# uC.net
KiCad netlist of a schematic drawn in Altium Designer
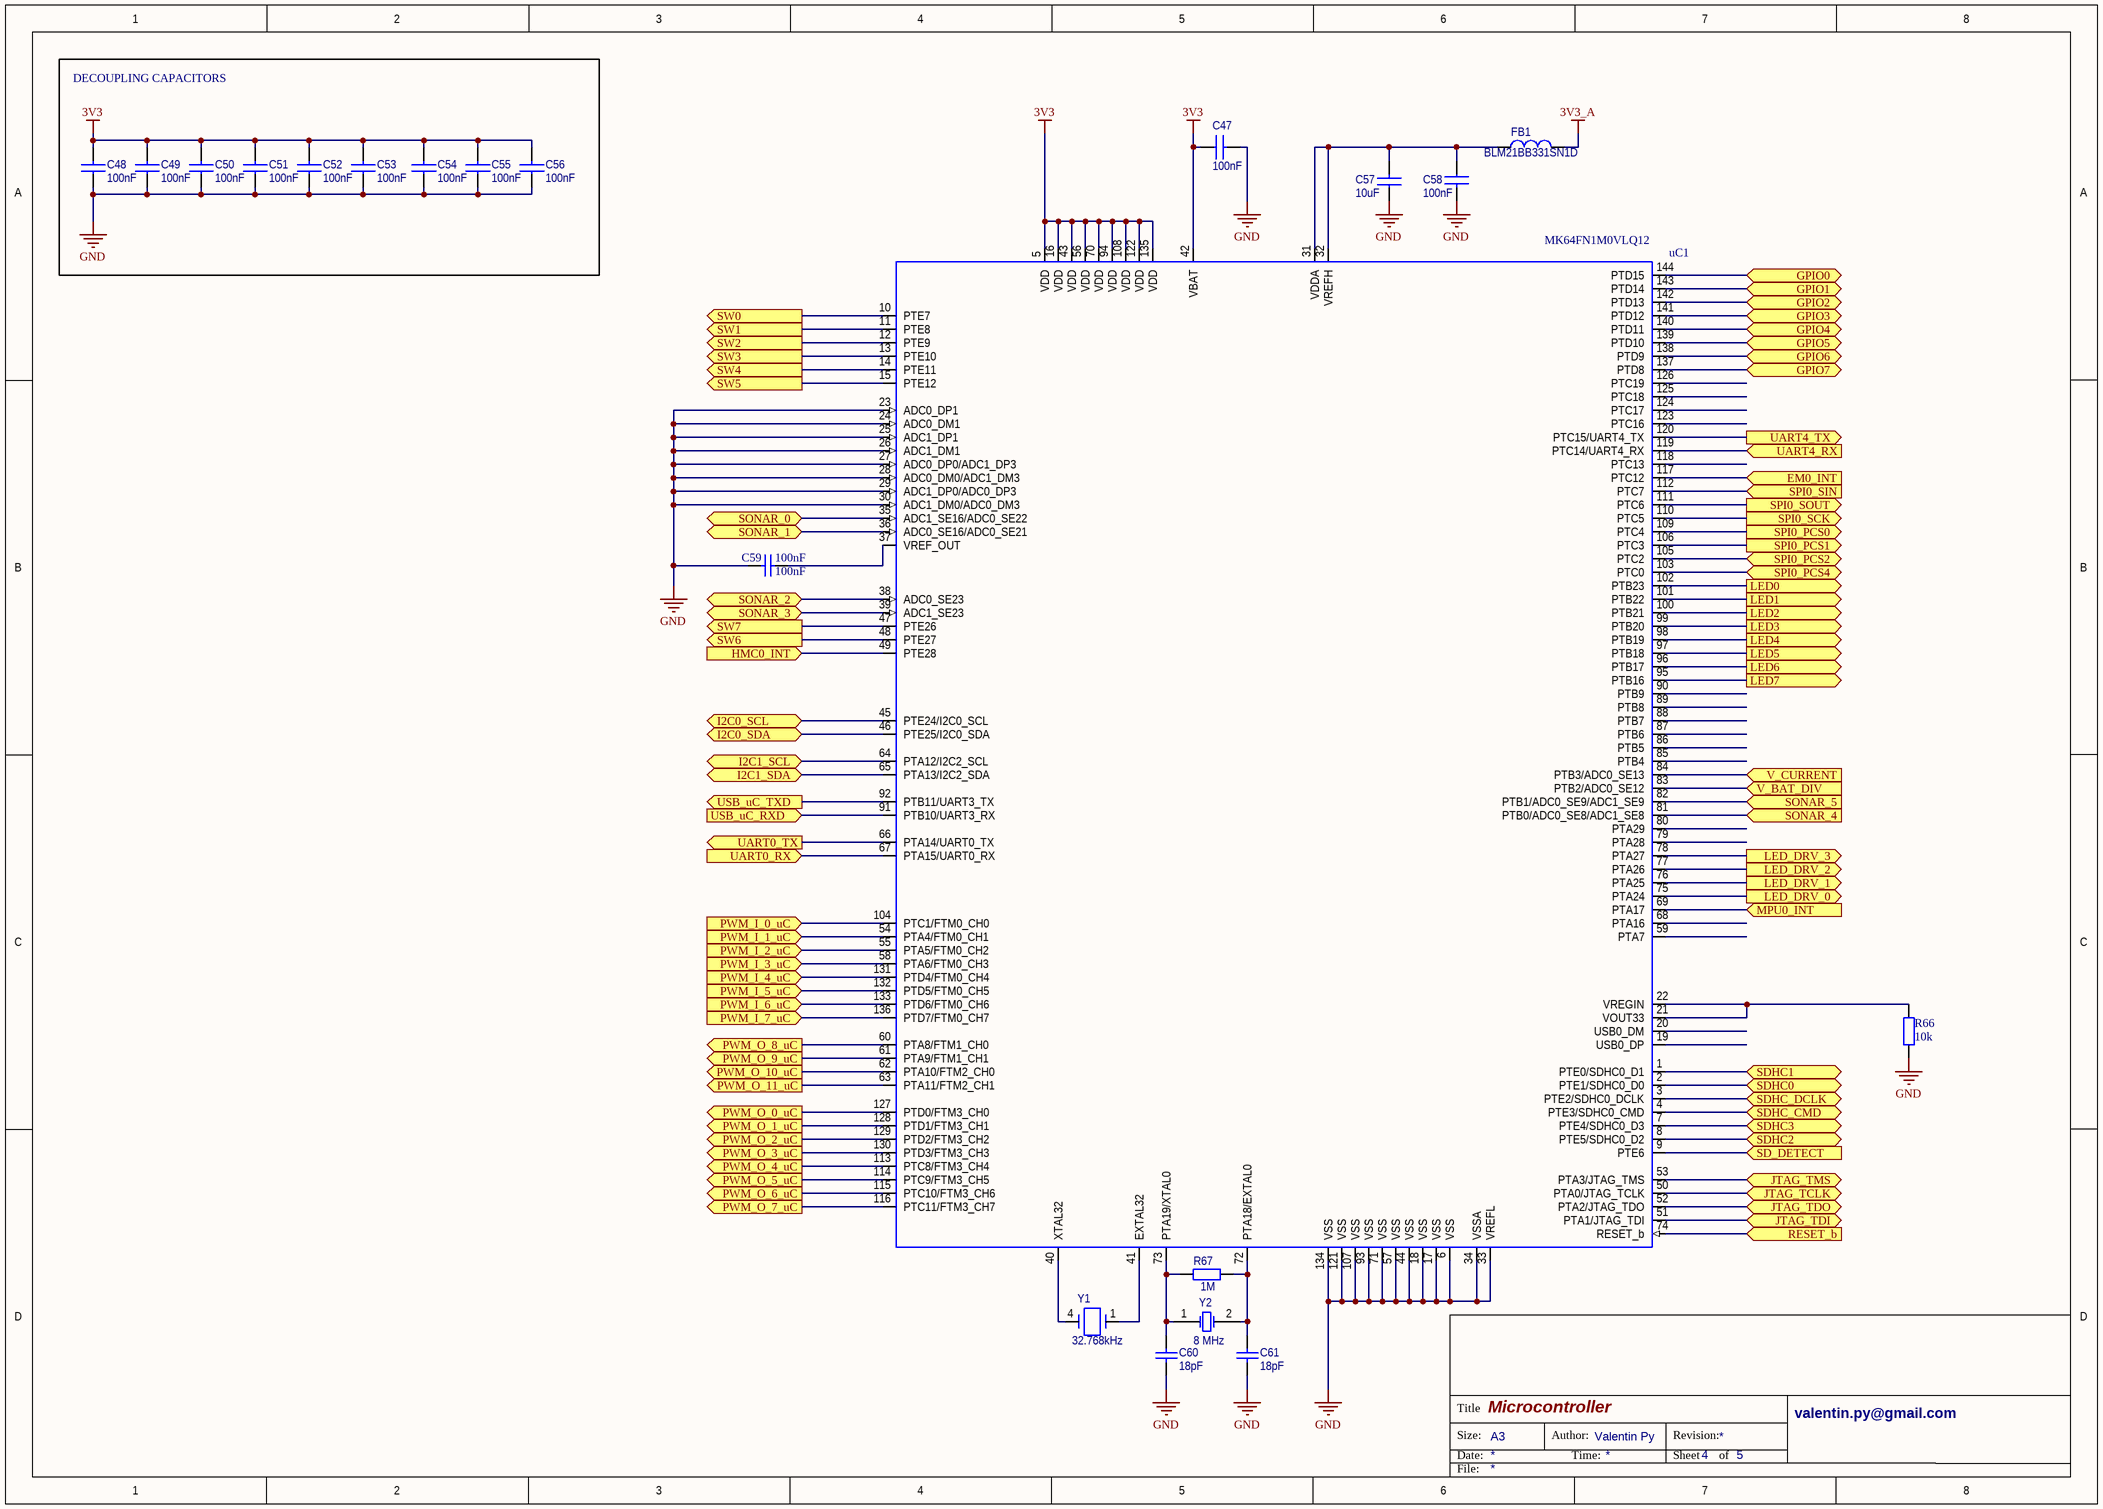
[diagram p0: uC.SchDoc]

(export (version "E")
  (design (tool "Eeschema 10.0.6"))
  (components
    (comp (ref "C47")
      (value "100nF")
      (footprint "080503")
      (description "CAP CER 0.1UF 25V 10% X7R 0805")
      (libsource (lib "EISI") (part "CAPA"))
    )
    (comp (ref "C48")
      (value "100nF")
      (footprint "080503")
      (description "CAP CER 0.1UF 25V 10% X7R 0805")
      (libsource (lib "EISI") (part "CAPA"))
    )
    (comp (ref "C49")
      (value "100nF")
      (footprint "080503")
      (description "CAP CER 0.1UF 25V 10% X7R 0805")
      (libsource (lib "EISI") (part "CAPA"))
    )
    (comp (ref "C50")
      (value "100nF")
      (footprint "080503")
      (description "CAP CER 0.1UF 25V 10% X7R 0805")
      (libsource (lib "EISI") (part "CAPA"))
    )
    (comp (ref "C51")
      (value "100nF")
      (footprint "080503")
      (description "CAP CER 0.1UF 25V 10% X7R 0805")
      (libsource (lib "EISI") (part "CAPA"))
    )
    (comp (ref "C52")
      (value "100nF")
      (footprint "080503")
      (description "CAP CER 0.1UF 25V 10% X7R 0805")
      (libsource (lib "EISI") (part "CAPA"))
    )
    (comp (ref "C53")
      (value "100nF")
      (footprint "080503")
      (description "CAP CER 0.1UF 25V 10% X7R 0805")
      (libsource (lib "EISI") (part "CAPA"))
    )
    (comp (ref "C54")
      (value "100nF")
      (footprint "080503")
      (description "CAP CER 0.1UF 25V 10% X7R 0805")
      (libsource (lib "EISI") (part "CAPA"))
    )
    (comp (ref "C55")
      (value "100nF")
      (footprint "080503")
      (description "CAP CER 0.1UF 25V 10% X7R 0805")
      (libsource (lib "EISI") (part "CAPA"))
    )
    (comp (ref "C56")
      (value "100nF")
      (footprint "080503")
      (description "CAP CER 0.1UF 25V 10% X7R 0805")
      (libsource (lib "EISI") (part "CAPA"))
    )
    (comp (ref "C57")
      (value "10uF")
      (footprint "080503")
      (description "CAP CER 10UF 16V 20% X6S 0805")
      (libsource (lib "EISI") (part "CAPA"))
    )
    (comp (ref "C58")
      (value "100nF")
      (footprint "080503")
      (description "CAP CER 0.1UF 25V 10% X7R 0805")
      (libsource (lib "EISI") (part "CAPA"))
    )
    (comp (ref "C59")
      (value "100nF")
      (footprint "080503")
      (description "CAP CER 0.1UF 25V 10% X7R 0805")
      (fields (field (name "ALTIUM_VALUE") "100nF"))
      (libsource (lib "Miscellaneous Devices") (part "Cap"))
    )
    (comp (ref "C60")
      (value "18pF")
      (footprint "060301")
      (description "CAP CER 18PF 50V 5% NP0 0603")
      (libsource (lib "Miscellaneous Devices") (part "Cap Semi"))
    )
    (comp (ref "C61")
      (value "18pF")
      (footprint "060301")
      (description "CAP CER 18PF 50V 5% NP0 0603")
      (libsource (lib "Miscellaneous Devices") (part "Cap Semi"))
    )
    (comp (ref "FB1")
      (value "BLM21BB331SN1D")
      (footprint "080501")
      (description "EMI Filter Beads, Chips & Arrays 0805 330 OHM")
      (libsource (lib "EISI") (part "Ferrite Bead"))
    )
    (comp (ref "R66")
      (value "10k")
      (footprint "060301")
      (description "RES 10K 0805")
      (libsource (lib "EISI") (part "RES"))
    )
    (comp (ref "R67")
      (value "1M")
      (footprint "060301")
      (description "RES 1M 0603")
      (libsource (lib "") (part "RES_1"))
    )
    (comp (ref "uC1")
      (value "MK64FN1M0VLQ12")
      (footprint "LQFP 144")
      (libsource (lib "Aeroval") (part "MK64FN1M0VLQ12"))
    )
    (comp (ref "Y1")
      (value "32.768kHz")
      (description "CRYSTAL 32.768 KHZ 12.5PF SMD")
      (fields (field (name "Comment") "CRYSTAL 32.768k"))
      (libsource (lib "*") (part "Crystal_32"))
    )
    (comp (ref "Y2")
      (value "8 MHz")
      (footprint "XT8_2-SMD")
      (description "CRYSTAL 8MHZ 18PF SMD")
      (fields (field (name "Comment") "ABM3-8.000MHZ-D2Y-T"))
      (libsource (lib "Miscellaneous Devices") (part "XTAL"))
    )
  )
  (nets
    (net (code "1") (name "/EM0_INT") (class "Default")
      (node (ref "uC1") (pin "117") (pinfunction "PTC12_117") (pintype "bidirectional"))
    )
    (net (code "2") (name "/GPIO0") (class "Default")
      (node (ref "uC1") (pin "144") (pinfunction "PTD15_144") (pintype "bidirectional"))
    )
    (net (code "3") (name "/GPIO1") (class "Default")
      (node (ref "uC1") (pin "143") (pinfunction "PTD14_143") (pintype "bidirectional"))
    )
    (net (code "4") (name "/GPIO2") (class "Default")
      (node (ref "uC1") (pin "142") (pinfunction "PTD13_142") (pintype "bidirectional"))
    )
    (net (code "5") (name "/GPIO3") (class "Default")
      (node (ref "uC1") (pin "141") (pinfunction "PTD12_141") (pintype "bidirectional"))
    )
    (net (code "6") (name "/GPIO4") (class "Default")
      (node (ref "uC1") (pin "140") (pinfunction "PTD11_140") (pintype "bidirectional"))
    )
    (net (code "7") (name "/GPIO5") (class "Default")
      (node (ref "uC1") (pin "139") (pinfunction "PTD10_139") (pintype "bidirectional"))
    )
    (net (code "8") (name "/GPIO6") (class "Default")
      (node (ref "uC1") (pin "138") (pinfunction "PTD9_138") (pintype "bidirectional"))
    )
    (net (code "9") (name "/GPIO7") (class "Default")
      (node (ref "uC1") (pin "137") (pinfunction "PTD8_137") (pintype "bidirectional"))
    )
    (net (code "10") (name "/HMC0_INT") (class "Default")
      (node (ref "uC1") (pin "49") (pinfunction "PTE28_49") (pintype "bidirectional"))
    )
    (net (code "11") (name "/I2C0_SCL") (class "Default")
      (node (ref "uC1") (pin "45") (pinfunction "PTE24/I2C0_SCL_45") (pintype "bidirectional"))
    )
    (net (code "12") (name "/I2C0_SDA") (class "Default")
      (node (ref "uC1") (pin "46") (pinfunction "PTE25/I2C0_SDA_46") (pintype "bidirectional"))
    )
    (net (code "13") (name "/I2C1_SCL") (class "Default")
      (node (ref "uC1") (pin "64") (pinfunction "PTA12/I2C2_SCL_64") (pintype "bidirectional"))
    )
    (net (code "14") (name "/I2C1_SDA") (class "Default")
      (node (ref "uC1") (pin "65") (pinfunction "PTA13/I2C2_SDA_65") (pintype "bidirectional"))
    )
    (net (code "15") (name "/JTAG_TCLK") (class "Default")
      (node (ref "uC1") (pin "50") (pinfunction "PTA0/JTAG_TCLK_50") (pintype "bidirectional"))
    )
    (net (code "16") (name "/JTAG_TDI") (class "Default")
      (node (ref "uC1") (pin "51") (pinfunction "PTA1/JTAG_TDI_51") (pintype "bidirectional"))
    )
    (net (code "17") (name "/JTAG_TDO") (class "Default")
      (node (ref "uC1") (pin "52") (pinfunction "PTA2/JTAG_TDO_52") (pintype "bidirectional"))
    )
    (net (code "18") (name "/JTAG_TMS") (class "Default")
      (node (ref "uC1") (pin "53") (pinfunction "PTA3/JTAG_TMS_53") (pintype "bidirectional"))
    )
    (net (code "19") (name "/LED0") (class "Default")
      (node (ref "uC1") (pin "102") (pinfunction "PTB23_102") (pintype "bidirectional"))
    )
    (net (code "20") (name "/LED1") (class "Default")
      (node (ref "uC1") (pin "101") (pinfunction "PTB22_101") (pintype "bidirectional"))
    )
    (net (code "21") (name "/LED2") (class "Default")
      (node (ref "uC1") (pin "100") (pinfunction "PTB21_100") (pintype "bidirectional"))
    )
    (net (code "22") (name "/LED3") (class "Default")
      (node (ref "uC1") (pin "99") (pinfunction "PTB20_99") (pintype "bidirectional"))
    )
    (net (code "23") (name "/LED4") (class "Default")
      (node (ref "uC1") (pin "98") (pinfunction "PTB19_98") (pintype "bidirectional"))
    )
    (net (code "24") (name "/LED5") (class "Default")
      (node (ref "uC1") (pin "97") (pinfunction "PTB18_97") (pintype "bidirectional"))
    )
    (net (code "25") (name "/LED6") (class "Default")
      (node (ref "uC1") (pin "96") (pinfunction "PTB17_96") (pintype "bidirectional"))
    )
    (net (code "26") (name "/LED7") (class "Default")
      (node (ref "uC1") (pin "95") (pinfunction "PTB16_95") (pintype "bidirectional"))
    )
    (net (code "27") (name "/LED_DRV_0") (class "Default")
      (node (ref "uC1") (pin "75") (pinfunction "PTA24_75") (pintype "bidirectional"))
    )
    (net (code "28") (name "/LED_DRV_1") (class "Default")
      (node (ref "uC1") (pin "76") (pinfunction "PTA25_76") (pintype "bidirectional"))
    )
    (net (code "29") (name "/LED_DRV_2") (class "Default")
      (node (ref "uC1") (pin "77") (pinfunction "PTA26_77") (pintype "bidirectional"))
    )
    (net (code "30") (name "/LED_DRV_3") (class "Default")
      (node (ref "uC1") (pin "78") (pinfunction "PTA27_78") (pintype "bidirectional"))
    )
    (net (code "31") (name "/MPU0_INT") (class "Default")
      (node (ref "uC1") (pin "69") (pinfunction "PTA17_69") (pintype "bidirectional"))
    )
    (net (code "32") (name "/PWM_I_0_uC") (class "Default")
      (node (ref "uC1") (pin "104") (pinfunction "PTC1/FTM0_CH0_104") (pintype "bidirectional"))
    )
    (net (code "33") (name "/PWM_I_1_uC") (class "Default")
      (node (ref "uC1") (pin "54") (pinfunction "PTA4/FTM0_CH1_54") (pintype "bidirectional"))
    )
    (net (code "34") (name "/PWM_I_2_uC") (class "Default")
      (node (ref "uC1") (pin "55") (pinfunction "PTA5/FTM0_CH2_55") (pintype "bidirectional"))
    )
    (net (code "35") (name "/PWM_I_3_uC") (class "Default")
      (node (ref "uC1") (pin "58") (pinfunction "PTA6/FTM0_CH3_58") (pintype "bidirectional"))
    )
    (net (code "36") (name "/PWM_I_4_uC") (class "Default")
      (node (ref "uC1") (pin "131") (pinfunction "PTD4/FTM0_CH4_131") (pintype "bidirectional"))
    )
    (net (code "37") (name "/PWM_I_5_uC") (class "Default")
      (node (ref "uC1") (pin "132") (pinfunction "PTD5/FTM0_CH5_132") (pintype "bidirectional"))
    )
    (net (code "38") (name "/PWM_I_6_uC") (class "Default")
      (node (ref "uC1") (pin "133") (pinfunction "PTD6/FTM0_CH6_133") (pintype "bidirectional"))
    )
    (net (code "39") (name "/PWM_I_7_uC") (class "Default")
      (node (ref "uC1") (pin "136") (pinfunction "PTD7/FTM0_CH7_136") (pintype "bidirectional"))
    )
    (net (code "40") (name "/PWM_O_0_uC") (class "Default")
      (node (ref "uC1") (pin "127") (pinfunction "PTD0/FTM3_CH0_127") (pintype "bidirectional"))
    )
    (net (code "41") (name "/PWM_O_1_uC") (class "Default")
      (node (ref "uC1") (pin "128") (pinfunction "PTD1/FTM3_CH1_128") (pintype "bidirectional"))
    )
    (net (code "42") (name "/PWM_O_2_uC") (class "Default")
      (node (ref "uC1") (pin "129") (pinfunction "PTD2/FTM3_CH2_129") (pintype "bidirectional"))
    )
    (net (code "43") (name "/PWM_O_3_uC") (class "Default")
      (node (ref "uC1") (pin "130") (pinfunction "PTD3/FTM3_CH3_130") (pintype "bidirectional"))
    )
    (net (code "44") (name "/PWM_O_4_uC") (class "Default")
      (node (ref "uC1") (pin "113") (pinfunction "PTC8/FTM3_CH4_113") (pintype "bidirectional"))
    )
    (net (code "45") (name "/PWM_O_5_uC") (class "Default")
      (node (ref "uC1") (pin "114") (pinfunction "PTC9/FTM3_CH5_114") (pintype "bidirectional"))
    )
    (net (code "46") (name "/PWM_O_6_uC") (class "Default")
      (node (ref "uC1") (pin "115") (pinfunction "PTC10/FTM3_CH6_115") (pintype "bidirectional"))
    )
    (net (code "47") (name "/PWM_O_7_uC") (class "Default")
      (node (ref "uC1") (pin "116") (pinfunction "PTC11/FTM3_CH7_116") (pintype "bidirectional"))
    )
    (net (code "48") (name "/PWM_O_8_uC") (class "Default")
      (node (ref "uC1") (pin "60") (pinfunction "PTA8/FTM1_CH0_60") (pintype "bidirectional"))
    )
    (net (code "49") (name "/PWM_O_9_uC") (class "Default")
      (node (ref "uC1") (pin "61") (pinfunction "PTA9/FTM1_CH1_61") (pintype "bidirectional"))
    )
    (net (code "50") (name "/PWM_O_10_uC") (class "Default")
      (node (ref "uC1") (pin "62") (pinfunction "PTA10/FTM2_CH0_62") (pintype "bidirectional"))
    )
    (net (code "51") (name "/PWM_O_11_uC") (class "Default")
      (node (ref "uC1") (pin "63") (pinfunction "PTA11/FTM2_CH1_63") (pintype "bidirectional"))
    )
    (net (code "52") (name "/RESET_b") (class "Default")
      (node (ref "uC1") (pin "74") (pinfunction "RESET_b_74") (pintype "input"))
    )
    (net (code "53") (name "/SDHC0") (class "Default")
      (node (ref "uC1") (pin "2") (pinfunction "PTE1/SDHC0_D0_2") (pintype "bidirectional"))
    )
    (net (code "54") (name "/SDHC1") (class "Default")
      (node (ref "uC1") (pin "1") (pinfunction "PTE0/SDHC0_D1_1") (pintype "bidirectional"))
    )
    (net (code "55") (name "/SDHC2") (class "Default")
      (node (ref "uC1") (pin "8") (pinfunction "PTE5/SDHC0_D2_8") (pintype "bidirectional"))
    )
    (net (code "56") (name "/SDHC3") (class "Default")
      (node (ref "uC1") (pin "7") (pinfunction "PTE4/SDHC0_D3_7") (pintype "bidirectional"))
    )
    (net (code "57") (name "/SDHC_CMD") (class "Default")
      (node (ref "uC1") (pin "4") (pinfunction "PTE3/SDHC0_CMD_4") (pintype "bidirectional"))
    )
    (net (code "58") (name "/SDHC_DCLK") (class "Default")
      (node (ref "uC1") (pin "3") (pinfunction "PTE2/SDHC0_DCLK_3") (pintype "bidirectional"))
    )
    (net (code "59") (name "/SD_DETECT") (class "Default")
      (node (ref "uC1") (pin "9") (pinfunction "PTE6_9") (pintype "bidirectional"))
    )
    (net (code "60") (name "/SONAR_0") (class "Default")
      (node (ref "uC1") (pin "35") (pinfunction "ADC1_SE16/ADC0_SE22_35") (pintype "input"))
    )
    (net (code "61") (name "/SONAR_1") (class "Default")
      (node (ref "uC1") (pin "36") (pinfunction "ADC0_SE16/ADC0_SE21_36") (pintype "input"))
    )
    (net (code "62") (name "/SONAR_2") (class "Default")
      (node (ref "uC1") (pin "38") (pinfunction "ADC0_SE23_38") (pintype "input"))
    )
    (net (code "63") (name "/SONAR_3") (class "Default")
      (node (ref "uC1") (pin "39") (pinfunction "ADC1_SE23_39") (pintype "input"))
    )
    (net (code "64") (name "/SONAR_4") (class "Default")
      (node (ref "uC1") (pin "81") (pinfunction "PTB0/ADC0_SE8/ADC1_SE8_81") (pintype "bidirectional"))
    )
    (net (code "65") (name "/SONAR_5") (class "Default")
      (node (ref "uC1") (pin "82") (pinfunction "PTB1/ADC0_SE9/ADC1_SE9_82") (pintype "bidirectional"))
    )
    (net (code "66") (name "/SPI0_PCS0") (class "Default")
      (node (ref "uC1") (pin "109") (pinfunction "PTC4_109") (pintype "bidirectional"))
    )
    (net (code "67") (name "/SPI0_PCS1") (class "Default")
      (node (ref "uC1") (pin "106") (pinfunction "PTC3_106") (pintype "bidirectional"))
    )
    (net (code "68") (name "/SPI0_PCS2") (class "Default")
      (node (ref "uC1") (pin "105") (pinfunction "PTC2_105") (pintype "bidirectional"))
    )
    (net (code "69") (name "/SPI0_PCS4") (class "Default")
      (node (ref "uC1") (pin "103") (pinfunction "PTC0_103") (pintype "bidirectional"))
    )
    (net (code "70") (name "/SPI0_SCK") (class "Default")
      (node (ref "uC1") (pin "110") (pinfunction "PTC5_110") (pintype "bidirectional"))
    )
    (net (code "71") (name "/SPI0_SIN") (class "Default")
      (node (ref "uC1") (pin "112") (pinfunction "PTC7_112") (pintype "bidirectional"))
    )
    (net (code "72") (name "/SPI0_SOUT") (class "Default")
      (node (ref "uC1") (pin "111") (pinfunction "PTC6_111") (pintype "bidirectional"))
    )
    (net (code "73") (name "/SW0") (class "Default")
      (node (ref "uC1") (pin "10") (pinfunction "PTE7_10") (pintype "bidirectional"))
    )
    (net (code "74") (name "/SW1") (class "Default")
      (node (ref "uC1") (pin "11") (pinfunction "PTE8_11") (pintype "bidirectional"))
    )
    (net (code "75") (name "/SW2") (class "Default")
      (node (ref "uC1") (pin "12") (pinfunction "PTE9_12") (pintype "bidirectional"))
    )
    (net (code "76") (name "/SW3") (class "Default")
      (node (ref "uC1") (pin "13") (pinfunction "PTE10_13") (pintype "bidirectional"))
    )
    (net (code "77") (name "/SW4") (class "Default")
      (node (ref "uC1") (pin "14") (pinfunction "PTE11_14") (pintype "bidirectional"))
    )
    (net (code "78") (name "/SW5") (class "Default")
      (node (ref "uC1") (pin "15") (pinfunction "PTE12_15") (pintype "bidirectional"))
    )
    (net (code "79") (name "/SW6") (class "Default")
      (node (ref "uC1") (pin "48") (pinfunction "PTE27_48") (pintype "bidirectional"))
    )
    (net (code "80") (name "/SW7") (class "Default")
      (node (ref "uC1") (pin "47") (pinfunction "PTE26_47") (pintype "bidirectional"))
    )
    (net (code "81") (name "/UART0_RX") (class "Default")
      (node (ref "uC1") (pin "67") (pinfunction "PTA15/UART0_RX_67") (pintype "bidirectional"))
    )
    (net (code "82") (name "/UART0_TX") (class "Default")
      (node (ref "uC1") (pin "66") (pinfunction "PTA14/UART0_TX_66") (pintype "bidirectional"))
    )
    (net (code "83") (name "/UART4_RX") (class "Default")
      (node (ref "uC1") (pin "119") (pinfunction "PTC14/UART4_RX_119") (pintype "bidirectional"))
    )
    (net (code "84") (name "/UART4_TX") (class "Default")
      (node (ref "uC1") (pin "120") (pinfunction "PTC15/UART4_TX_120") (pintype "bidirectional"))
    )
    (net (code "85") (name "/USB_uC_RXD") (class "Default")
      (node (ref "uC1") (pin "91") (pinfunction "PTB10/UART3_RX_91") (pintype "bidirectional"))
    )
    (net (code "86") (name "/USB_uC_TXD") (class "Default")
      (node (ref "uC1") (pin "92") (pinfunction "PTB11/UART3_TX_92") (pintype "bidirectional"))
    )
    (net (code "87") (name "/V_BAT_DIV") (class "Default")
      (node (ref "uC1") (pin "83") (pinfunction "PTB2/ADC0_SE12_83") (pintype "bidirectional"))
    )
    (net (code "88") (name "/V_CURRENT") (class "Default")
      (node (ref "uC1") (pin "84") (pinfunction "PTB3/ADC0_SE13_84") (pintype "bidirectional"))
    )
    (net (code "89") (name "3V3") (class "Default")
      (node (ref "C47") (pin "1") (pinfunction "1_1") (pintype "passive"))
      (node (ref "C48") (pin "2") (pinfunction "2_2") (pintype "passive"))
      (node (ref "C49") (pin "2") (pinfunction "2_2") (pintype "passive"))
      (node (ref "C50") (pin "2") (pinfunction "2_2") (pintype "passive"))
      (node (ref "C51") (pin "2") (pinfunction "2_2") (pintype "passive"))
      (node (ref "C52") (pin "2") (pinfunction "2_2") (pintype "passive"))
      (node (ref "C53") (pin "2") (pinfunction "2_2") (pintype "passive"))
      (node (ref "C54") (pin "2") (pinfunction "2_2") (pintype "passive"))
      (node (ref "C55") (pin "2") (pinfunction "2_2") (pintype "passive"))
      (node (ref "C56") (pin "2") (pinfunction "2_2") (pintype "passive"))
      (node (ref "uC1") (pin "108") (pinfunction "VDD_108") (pintype "power_in"))
      (node (ref "uC1") (pin "122") (pinfunction "VDD_122") (pintype "power_in"))
      (node (ref "uC1") (pin "135") (pinfunction "VDD_135") (pintype "power_in"))
      (node (ref "uC1") (pin "16") (pinfunction "VDD_16") (pintype "power_in"))
      (node (ref "uC1") (pin "42") (pinfunction "VBAT_42") (pintype "power_in"))
      (node (ref "uC1") (pin "43") (pinfunction "VDD_43") (pintype "power_in"))
      (node (ref "uC1") (pin "5") (pinfunction "VDD_5") (pintype "power_in"))
      (node (ref "uC1") (pin "56") (pinfunction "VDD_56") (pintype "power_in"))
      (node (ref "uC1") (pin "70") (pinfunction "VDD_70") (pintype "power_in"))
      (node (ref "uC1") (pin "94") (pinfunction "VDD_94") (pintype "power_in"))
    )
    (net (code "90") (name "3V3_A") (class "Default")
      (node (ref "FB1") (pin "2") (pinfunction "2_2") (pintype "passive"))
    )
    (net (code "91") (name "GND") (class "Default")
      (node (ref "C47") (pin "2") (pinfunction "2_2") (pintype "passive"))
      (node (ref "C48") (pin "1") (pinfunction "1_1") (pintype "passive"))
      (node (ref "C49") (pin "1") (pinfunction "1_1") (pintype "passive"))
      (node (ref "C50") (pin "1") (pinfunction "1_1") (pintype "passive"))
      (node (ref "C51") (pin "1") (pinfunction "1_1") (pintype "passive"))
      (node (ref "C52") (pin "1") (pinfunction "1_1") (pintype "passive"))
      (node (ref "C53") (pin "1") (pinfunction "1_1") (pintype "passive"))
      (node (ref "C54") (pin "1") (pinfunction "1_1") (pintype "passive"))
      (node (ref "C55") (pin "1") (pinfunction "1_1") (pintype "passive"))
      (node (ref "C56") (pin "1") (pinfunction "1_1") (pintype "passive"))
      (node (ref "C57") (pin "1") (pinfunction "1_1") (pintype "passive"))
      (node (ref "C58") (pin "2") (pinfunction "2_2") (pintype "passive"))
      (node (ref "C59") (pin "2") (pinfunction "2_2") (pintype "passive"))
      (node (ref "C60") (pin "1") (pinfunction "1_1") (pintype "passive"))
      (node (ref "C61") (pin "1") (pinfunction "1_1") (pintype "passive"))
      (node (ref "R66") (pin "1") (pinfunction "1_1") (pintype "passive"))
      (node (ref "uC1") (pin "107") (pinfunction "VSS_107") (pintype "power_in"))
      (node (ref "uC1") (pin "121") (pinfunction "VSS_121") (pintype "power_in"))
      (node (ref "uC1") (pin "134") (pinfunction "VSS_134") (pintype "power_in"))
      (node (ref "uC1") (pin "17") (pinfunction "VSS_17") (pintype "power_in"))
      (node (ref "uC1") (pin "18") (pinfunction "VSS_18") (pintype "power_in"))
      (node (ref "uC1") (pin "23") (pinfunction "ADC0_DP1_23") (pintype "input"))
      (node (ref "uC1") (pin "24") (pinfunction "ADC0_DM1_24") (pintype "input"))
      (node (ref "uC1") (pin "25") (pinfunction "ADC1_DP1_25") (pintype "input"))
      (node (ref "uC1") (pin "26") (pinfunction "ADC1_DM1_26") (pintype "input"))
      (node (ref "uC1") (pin "27") (pinfunction "ADC0_DP0/ADC1_DP3_27") (pintype "input"))
      (node (ref "uC1") (pin "28") (pinfunction "ADC0_DM0/ADC1_DM3_28") (pintype "input"))
      (node (ref "uC1") (pin "29") (pinfunction "ADC1_DP0/ADC0_DP3_29") (pintype "input"))
      (node (ref "uC1") (pin "30") (pinfunction "ADC1_DM0/ADC0_DM3_30") (pintype "input"))
      (node (ref "uC1") (pin "33") (pinfunction "VREFL_33") (pintype "power_in"))
      (node (ref "uC1") (pin "34") (pinfunction "VSSA_34") (pintype "power_in"))
      (node (ref "uC1") (pin "44") (pinfunction "VSS_44") (pintype "power_in"))
      (node (ref "uC1") (pin "57") (pinfunction "VSS_57") (pintype "power_in"))
      (node (ref "uC1") (pin "6") (pinfunction "VSS_6") (pintype "power_in"))
      (node (ref "uC1") (pin "71") (pinfunction "VSS_71") (pintype "power_in"))
      (node (ref "uC1") (pin "93") (pinfunction "VSS_93") (pintype "power_in"))
    )
    (net (code "92") (name "Net-(Y2-OSC1)") (class "Default")
      (node (ref "C60") (pin "2") (pinfunction "2_2") (pintype "passive"))
      (node (ref "R67") (pin "1") (pinfunction "1_1") (pintype "passive"))
      (node (ref "Y2") (pin "1") (pinfunction "OSC1_1") (pintype "passive"))
      (node (ref "uC1") (pin "73") (pinfunction "PTA19/XTAL0_73") (pintype "bidirectional"))
    )
    (net (code "93") (name "Net-(Y2-OSC2)") (class "Default")
      (node (ref "C61") (pin "2") (pinfunction "2_2") (pintype "passive"))
      (node (ref "R67") (pin "2") (pinfunction "2_2") (pintype "passive"))
      (node (ref "Y2") (pin "2") (pinfunction "OSC2_2") (pintype "passive"))
      (node (ref "uC1") (pin "72") (pinfunction "PTA18/EXTAL0_72") (pintype "bidirectional"))
    )
    (net (code "94") (name "Net-(uC1-EXTAL32)") (class "Default")
      (node (ref "Y1") (pin "1") (pinfunction "1_1") (pintype "passive"))
      (node (ref "uC1") (pin "41") (pinfunction "EXTAL32_41") (pintype "bidirectional"))
    )
    (net (code "95") (name "Net-(uC1-VDDA)") (class "Default")
      (node (ref "C57") (pin "2") (pinfunction "2_2") (pintype "passive"))
      (node (ref "C58") (pin "1") (pinfunction "1_1") (pintype "passive"))
      (node (ref "FB1") (pin "1") (pinfunction "1_1") (pintype "passive"))
      (node (ref "uC1") (pin "31") (pinfunction "VDDA_31") (pintype "power_in"))
      (node (ref "uC1") (pin "32") (pinfunction "VREFH_32") (pintype "power_in"))
    )
    (net (code "96") (name "Net-(uC1-VOUT33)") (class "Default")
      (node (ref "R66") (pin "2") (pinfunction "2_2") (pintype "passive"))
      (node (ref "uC1") (pin "21") (pinfunction "VOUT33_21") (pintype "power_in"))
      (node (ref "uC1") (pin "22") (pinfunction "VREGIN_22") (pintype "power_in"))
    )
    (net (code "97") (name "Net-(uC1-VREF_OUT)") (class "Default")
      (node (ref "C59") (pin "1") (pinfunction "1_1") (pintype "passive"))
      (node (ref "uC1") (pin "37") (pinfunction "VREF_OUT_37") (pintype "power_in"))
    )
    (net (code "98") (name "Net-(uC1-XTAL32)") (class "Default")
      (node (ref "Y1") (pin "4") (pinfunction "4_4") (pintype "passive"))
      (node (ref "uC1") (pin "40") (pinfunction "XTAL32_40") (pintype "bidirectional"))
    )
    (net (code "99") (name "unconnected-(uC1-PTA7-Pad59)") (class "Default")
      (node (ref "uC1") (pin "59") (pinfunction "PTA7_59") (pintype "bidirectional"))
    )
    (net (code "100") (name "unconnected-(uC1-PTA16-Pad68)") (class "Default")
      (node (ref "uC1") (pin "68") (pinfunction "PTA16_68") (pintype "bidirectional"))
    )
    (net (code "101") (name "unconnected-(uC1-PTA28-Pad79)") (class "Default")
      (node (ref "uC1") (pin "79") (pinfunction "PTA28_79") (pintype "bidirectional"))
    )
    (net (code "102") (name "unconnected-(uC1-PTA29-Pad80)") (class "Default")
      (node (ref "uC1") (pin "80") (pinfunction "PTA29_80") (pintype "bidirectional"))
    )
    (net (code "103") (name "unconnected-(uC1-PTB4-Pad85)") (class "Default")
      (node (ref "uC1") (pin "85") (pinfunction "PTB4_85") (pintype "bidirectional"))
    )
    (net (code "104") (name "unconnected-(uC1-PTB5-Pad86)") (class "Default")
      (node (ref "uC1") (pin "86") (pinfunction "PTB5_86") (pintype "bidirectional"))
    )
    (net (code "105") (name "unconnected-(uC1-PTB6-Pad87)") (class "Default")
      (node (ref "uC1") (pin "87") (pinfunction "PTB6_87") (pintype "bidirectional"))
    )
    (net (code "106") (name "unconnected-(uC1-PTB7-Pad88)") (class "Default")
      (node (ref "uC1") (pin "88") (pinfunction "PTB7_88") (pintype "bidirectional"))
    )
    (net (code "107") (name "unconnected-(uC1-PTB8-Pad89)") (class "Default")
      (node (ref "uC1") (pin "89") (pinfunction "PTB8_89") (pintype "bidirectional"))
    )
    (net (code "108") (name "unconnected-(uC1-PTB9-Pad90)") (class "Default")
      (node (ref "uC1") (pin "90") (pinfunction "PTB9_90") (pintype "bidirectional"))
    )
    (net (code "109") (name "unconnected-(uC1-PTC13-Pad118)") (class "Default")
      (node (ref "uC1") (pin "118") (pinfunction "PTC13_118") (pintype "bidirectional"))
    )
    (net (code "110") (name "unconnected-(uC1-PTC16-Pad123)") (class "Default")
      (node (ref "uC1") (pin "123") (pinfunction "PTC16_123") (pintype "bidirectional"))
    )
    (net (code "111") (name "unconnected-(uC1-PTC17-Pad124)") (class "Default")
      (node (ref "uC1") (pin "124") (pinfunction "PTC17_124") (pintype "bidirectional"))
    )
    (net (code "112") (name "unconnected-(uC1-PTC18-Pad125)") (class "Default")
      (node (ref "uC1") (pin "125") (pinfunction "PTC18_125") (pintype "bidirectional"))
    )
    (net (code "113") (name "unconnected-(uC1-PTC19-Pad126)") (class "Default")
      (node (ref "uC1") (pin "126") (pinfunction "PTC19_126") (pintype "bidirectional"))
    )
    (net (code "114") (name "unconnected-(uC1-USB0_DM-Pad20)") (class "Default")
      (node (ref "uC1") (pin "20") (pinfunction "USB0_DM_20") (pintype "bidirectional"))
    )
    (net (code "115") (name "unconnected-(uC1-USB0_DP-Pad19)") (class "Default")
      (node (ref "uC1") (pin "19") (pinfunction "USB0_DP_19") (pintype "bidirectional"))
    )
  )
)
